# circuit.net
KiCad netlist of a schematic drawn in EAGLE
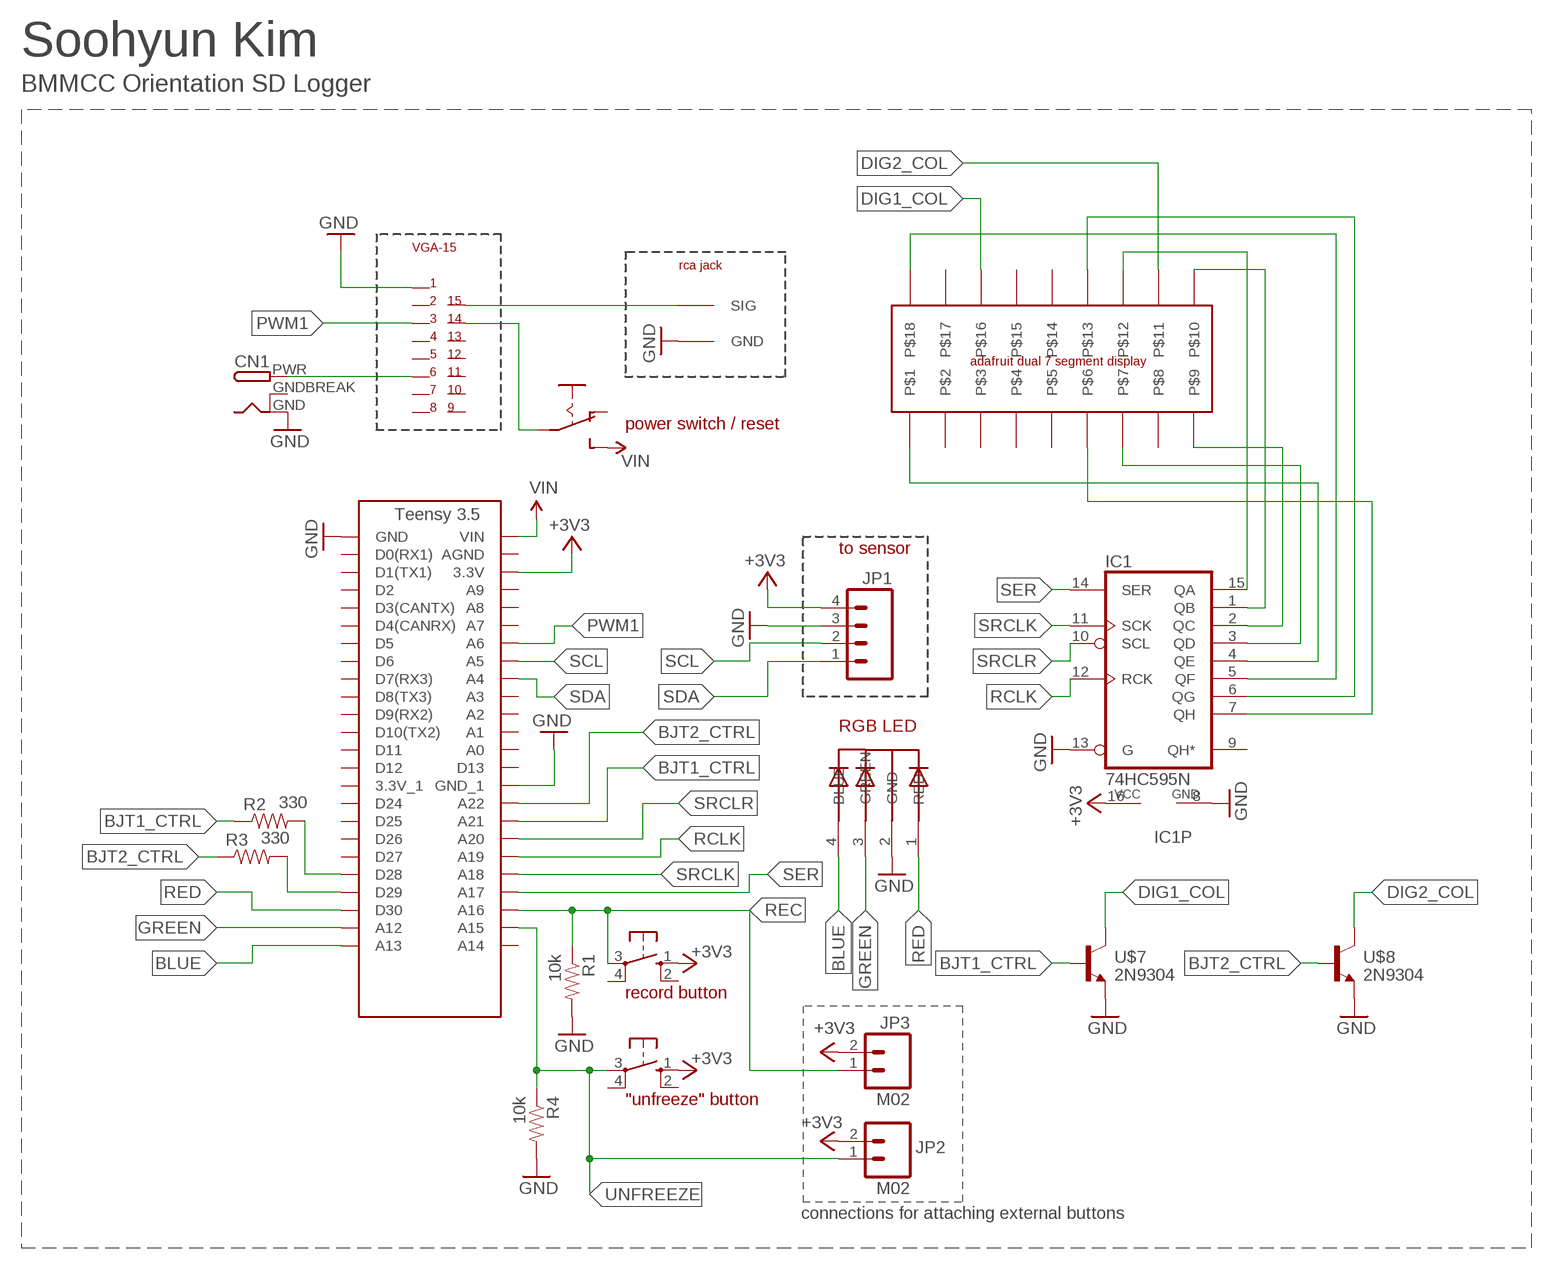
[diagram p0: schematic, sheet 1]

(export (version "E")
  (design (tool "Eeschema 10.0.6"))
  (components
    (comp (ref "CN1")
      (value "DCBARRELPTH")
      (footprint "eagle-import:DCJACK_2MM_PTH")
      (libsource (lib "eagle-import") (part "DCBARRELPTH"))
    )
    (comp (ref "IC1")
      (value "74HC595N")
      (footprint "eagle-import:DIL16")
      (libsource (lib "eagle-import") (part "74595NHC"))
    )
    (comp (ref "JP1")
      (value "M04")
      (footprint "eagle-import:1X04")
      (libsource (lib "eagle-import") (part "M04"))
    )
    (comp (ref "JP2")
      (value "M02")
      (footprint "eagle-import:1X02")
      (libsource (lib "eagle-import") (part "M02"))
    )
    (comp (ref "JP3")
      (value "M02")
      (footprint "eagle-import:1X02")
      (libsource (lib "eagle-import") (part "M02"))
    )
    (comp (ref "R1")
      (value "10k")
      (footprint "eagle-import:AXIAL-0.4")
      (libsource (lib "eagle-import") (part "RESISTORPTH-1/4W"))
    )
    (comp (ref "R2")
      (value "330")
      (footprint "eagle-import:AXIAL-0.4")
      (libsource (lib "eagle-import") (part "RESISTORPTH-1/4W"))
    )
    (comp (ref "R3")
      (value "330")
      (footprint "eagle-import:AXIAL-0.4")
      (libsource (lib "eagle-import") (part "RESISTORPTH-1/4W"))
    )
    (comp (ref "R4")
      (value "10k")
      (footprint "eagle-import:AXIAL-0.4")
      (libsource (lib "eagle-import") (part "RESISTORPTH-1/4W"))
    )
    (comp (ref "S3")
      (value "40-XX")
      (footprint "eagle-import:B3F-40XX")
      (fields (field (name "MF") "OMRON COMPONENTS USA") (field (name "MPN") "B3F-4000"))
      (libsource (lib "eagle-import") (part "40-XX"))
    )
    (comp (ref "S4")
      (value "40-XX")
      (footprint "eagle-import:B3F-40XX")
      (fields (field (name "MF") "OMRON COMPONENTS USA") (field (name "MPN") "B3F-4000"))
      (libsource (lib "eagle-import") (part "40-XX"))
    )
    (comp (ref "U$1")
      (value "TEENSY_3.5")
      (footprint "eagle-import:TEENSY_3.5_SIMPLE")
      (libsource (lib "eagle-import") (part "TEENSY_3.5"))
    )
    (comp (ref "U$2")
      (value "VGA-15")
      (footprint "eagle-import:VGA-15")
      (libsource (lib "eagle-import") (part "VGA-15"))
    )
    (comp (ref "U$3")
      (value "RCA")
      (footprint "eagle-import:RCA")
      (libsource (lib "eagle-import") (part "RCA"))
    )
    (comp (ref "U$4")
      (value "LED_5MM_RGB")
      (footprint "eagle-import:LED_5MM_RGB")
      (libsource (lib "eagle-import") (part "LED_5MM_RGB"))
    )
    (comp (ref "U$5")
      (value "SLIDE_SWITCH")
      (footprint "eagle-import:SLIDE_SWITCH")
      (libsource (lib "eagle-import") (part "SLIDE_SWITCH"))
    )
    (comp (ref "U$6")
      (value "DUAL_7SEG_DISPLAY")
      (footprint "eagle-import:DUAL_7SEG_DISPLAY")
      (libsource (lib "eagle-import") (part "DUAL_7SEG_DISPLAY"))
    )
    (comp (ref "U$7")
      (value "2N9304")
      (footprint "eagle-import:TO92")
      (libsource (lib "eagle-import") (part "2N9304"))
    )
    (comp (ref "U$8")
      (value "2N9304")
      (footprint "eagle-import:TO92")
      (libsource (lib "eagle-import") (part "2N9304"))
    )
  )
  (nets
    (net (code "1") (name "+3V3") (class "Default")
      (node (ref "IC1") (pin "16") (pinfunction "VCC_16") (pintype "power_in"))
      (node (ref "JP1") (pin "4") (pinfunction "4_4") (pintype "passive"))
      (node (ref "JP2") (pin "2") (pinfunction "2_2") (pintype "passive"))
      (node (ref "JP3") (pin "2") (pinfunction "2_2") (pintype "passive"))
      (node (ref "S3") (pin "1") (pinfunction "S_1") (pintype "passive"))
      (node (ref "S4") (pin "1") (pinfunction "S_1") (pintype "passive"))
      (node (ref "U$1") (pin "3.3V") (pinfunction "3.3V_3.3V") (pintype "bidirectional"))
    )
    (net (code "2") (name "/GNDBREAK") (class "Default")
      (node (ref "CN1") (pin "GNDBREAK") (pinfunction "GNDBREAK_GNDBREAK") (pintype "power_in"))
    )
    (net (code "3") (name "BJT1_CTRL") (class "Default")
      (node (ref "R2") (pin "P$1") (pinfunction "1_P$1") (pintype "passive"))
      (node (ref "U$1") (pin "A21") (pinfunction "A21_A21") (pintype "bidirectional"))
      (node (ref "U$7") (pin "2") (pinfunction "BASE_2") (pintype "passive"))
    )
    (net (code "4") (name "BJT2_CTRL") (class "Default")
      (node (ref "R3") (pin "P$1") (pinfunction "1_P$1") (pintype "passive"))
      (node (ref "U$1") (pin "A22") (pinfunction "A22_A22") (pintype "bidirectional"))
      (node (ref "U$8") (pin "2") (pinfunction "BASE_2") (pintype "passive"))
    )
    (net (code "5") (name "BLUE") (class "Default")
      (node (ref "U$1") (pin "A13") (pinfunction "A13_A13") (pintype "bidirectional"))
      (node (ref "U$4") (pin "4") (pinfunction "BLUE_4") (pintype "bidirectional"))
    )
    (net (code "6") (name "DIG1_COL") (class "Default")
      (node (ref "U$6") (pin "16") (pinfunction "P$16_16") (pintype "bidirectional"))
      (node (ref "U$7") (pin "1") (pinfunction "COLLECTOR_1") (pintype "passive"))
    )
    (net (code "7") (name "DIG2_COL") (class "Default")
      (node (ref "U$6") (pin "11") (pinfunction "P$11_11") (pintype "bidirectional"))
      (node (ref "U$8") (pin "1") (pinfunction "COLLECTOR_1") (pintype "passive"))
    )
    (net (code "8") (name "GND") (class "Default")
      (node (ref "CN1") (pin "GND") (pinfunction "GND_GND") (pintype "power_in"))
      (node (ref "IC1") (pin "13") (pinfunction "G_13") (pintype "input"))
      (node (ref "IC1") (pin "8") (pinfunction "GND_8") (pintype "power_in"))
      (node (ref "JP1") (pin "3") (pinfunction "3_3") (pintype "passive"))
      (node (ref "R1") (pin "P$2") (pinfunction "2_P$2") (pintype "passive"))
      (node (ref "R4") (pin "P$2") (pinfunction "2_P$2") (pintype "passive"))
      (node (ref "U$1") (pin "GND") (pinfunction "GND_GND") (pintype "bidirectional"))
      (node (ref "U$1") (pin "GND_1") (pinfunction "GND_1_GND_1") (pintype "bidirectional"))
      (node (ref "U$2") (pin "1") (pinfunction "P$1_1") (pintype "bidirectional"))
      (node (ref "U$3") (pin "GND") (pinfunction "GND_GND") (pintype "bidirectional"))
      (node (ref "U$4") (pin "2") (pinfunction "GND_2") (pintype "bidirectional"))
      (node (ref "U$7") (pin "3") (pinfunction "EMITTER_3") (pintype "passive"))
      (node (ref "U$8") (pin "3") (pinfunction "EMITTER_3") (pintype "passive"))
    )
    (net (code "9") (name "GREEN") (class "Default")
      (node (ref "U$1") (pin "A12") (pinfunction "A12_A12") (pintype "bidirectional"))
      (node (ref "U$4") (pin "3") (pinfunction "GREEN_3") (pintype "bidirectional"))
    )
    (net (code "10") (name "Net-(IC1A-QA)") (class "Default")
      (node (ref "IC1") (pin "15") (pinfunction "QA_15") (pintype "tri_state"))
      (node (ref "U$6") (pin "12") (pinfunction "P$12_12") (pintype "bidirectional"))
    )
    (net (code "11") (name "Net-(IC1A-QB)") (class "Default")
      (node (ref "IC1") (pin "1") (pinfunction "QB_1") (pintype "tri_state"))
      (node (ref "U$6") (pin "10") (pinfunction "P$10_10") (pintype "bidirectional"))
    )
    (net (code "12") (name "Net-(IC1A-QC)") (class "Default")
      (node (ref "IC1") (pin "2") (pinfunction "QC_2") (pintype "tri_state"))
      (node (ref "U$6") (pin "9") (pinfunction "P$9_9") (pintype "bidirectional"))
    )
    (net (code "13") (name "Net-(IC1A-QD)") (class "Default")
      (node (ref "IC1") (pin "3") (pinfunction "QD_3") (pintype "tri_state"))
      (node (ref "U$6") (pin "7") (pinfunction "P$7_7") (pintype "bidirectional"))
    )
    (net (code "14") (name "Net-(IC1A-QE)") (class "Default")
      (node (ref "IC1") (pin "4") (pinfunction "QE_4") (pintype "tri_state"))
      (node (ref "U$6") (pin "1") (pinfunction "P$1_1") (pintype "bidirectional"))
    )
    (net (code "15") (name "Net-(IC1A-QF)") (class "Default")
      (node (ref "IC1") (pin "5") (pinfunction "QF_5") (pintype "tri_state"))
      (node (ref "U$6") (pin "18") (pinfunction "P$18_18") (pintype "bidirectional"))
    )
    (net (code "16") (name "Net-(IC1A-QG)") (class "Default")
      (node (ref "IC1") (pin "6") (pinfunction "QG_6") (pintype "tri_state"))
      (node (ref "U$6") (pin "13") (pinfunction "P$13_13") (pintype "bidirectional"))
    )
    (net (code "17") (name "Net-(IC1A-QH)") (class "Default")
      (node (ref "IC1") (pin "7") (pinfunction "QH_7") (pintype "tri_state"))
      (node (ref "U$6") (pin "6") (pinfunction "P$6_6") (pintype "bidirectional"))
    )
    (net (code "18") (name "Net-(R2-2)") (class "Default")
      (node (ref "R2") (pin "P$2") (pinfunction "2_P$2") (pintype "passive"))
      (node (ref "U$1") (pin "D28") (pinfunction "D28_D28") (pintype "bidirectional"))
    )
    (net (code "19") (name "Net-(R3-2)") (class "Default")
      (node (ref "R3") (pin "P$2") (pinfunction "2_P$2") (pintype "passive"))
      (node (ref "U$1") (pin "D29") (pinfunction "D29_D29") (pintype "bidirectional"))
    )
    (net (code "20") (name "Net-(U$2-P$6)") (class "Default")
      (node (ref "CN1") (pin "PWR") (pinfunction "PWR_PWR") (pintype "power_in"))
      (node (ref "U$2") (pin "6") (pinfunction "P$6_6") (pintype "bidirectional"))
    )
    (net (code "21") (name "Net-(U$2-P$14)") (class "Default")
      (node (ref "U$2") (pin "14") (pinfunction "P$14_14") (pintype "bidirectional"))
      (node (ref "U$5") (pin "P$2") (pinfunction "P_P$2") (pintype "passive"))
    )
    (net (code "22") (name "Net-(U$2-P$15)") (class "Default")
      (node (ref "U$2") (pin "15") (pinfunction "P$15_15") (pintype "bidirectional"))
      (node (ref "U$3") (pin "SIG") (pinfunction "SIG_SIG") (pintype "bidirectional"))
    )
    (net (code "23") (name "PWM1") (class "Default")
      (node (ref "U$1") (pin "A6") (pinfunction "A6_A6") (pintype "bidirectional"))
      (node (ref "U$2") (pin "3") (pinfunction "P$3_3") (pintype "bidirectional"))
    )
    (net (code "24") (name "RCLK") (class "Default")
      (node (ref "IC1") (pin "12") (pinfunction "RCK_12") (pintype "input"))
      (node (ref "U$1") (pin "A19") (pinfunction "A19_A19") (pintype "bidirectional"))
    )
    (net (code "25") (name "REC") (class "Default")
      (node (ref "JP3") (pin "1") (pinfunction "1_1") (pintype "passive"))
      (node (ref "R1") (pin "P$1") (pinfunction "1_P$1") (pintype "passive"))
      (node (ref "S3") (pin "3") (pinfunction "P_3") (pintype "passive"))
      (node (ref "U$1") (pin "A16") (pinfunction "A16_A16") (pintype "bidirectional"))
    )
    (net (code "26") (name "RED") (class "Default")
      (node (ref "U$1") (pin "D30") (pinfunction "D30_D30") (pintype "bidirectional"))
      (node (ref "U$4") (pin "1") (pinfunction "RED_1") (pintype "bidirectional"))
    )
    (net (code "27") (name "SCL") (class "Default")
      (node (ref "JP1") (pin "2") (pinfunction "2_2") (pintype "passive"))
      (node (ref "U$1") (pin "A5") (pinfunction "A5_A5") (pintype "bidirectional"))
    )
    (net (code "28") (name "SDA") (class "Default")
      (node (ref "JP1") (pin "1") (pinfunction "1_1") (pintype "passive"))
      (node (ref "U$1") (pin "A4") (pinfunction "A4_A4") (pintype "bidirectional"))
    )
    (net (code "29") (name "SER") (class "Default")
      (node (ref "IC1") (pin "14") (pinfunction "SER_14") (pintype "input"))
      (node (ref "U$1") (pin "A17") (pinfunction "A17_A17") (pintype "bidirectional"))
    )
    (net (code "30") (name "SRCLK") (class "Default")
      (node (ref "IC1") (pin "11") (pinfunction "SCK_11") (pintype "input"))
      (node (ref "U$1") (pin "A18") (pinfunction "A18_A18") (pintype "bidirectional"))
    )
    (net (code "31") (name "SRCLR") (class "Default")
      (node (ref "IC1") (pin "10") (pinfunction "SCL_10") (pintype "input"))
      (node (ref "U$1") (pin "A20") (pinfunction "A20_A20") (pintype "bidirectional"))
    )
    (net (code "32") (name "UNFREEZE") (class "Default")
      (node (ref "JP2") (pin "1") (pinfunction "1_1") (pintype "passive"))
      (node (ref "R4") (pin "P$1") (pinfunction "1_P$1") (pintype "passive"))
      (node (ref "S4") (pin "3") (pinfunction "P_3") (pintype "passive"))
      (node (ref "U$1") (pin "A15") (pinfunction "A15_A15") (pintype "bidirectional"))
    )
    (net (code "33") (name "VIN") (class "Default")
      (node (ref "U$1") (pin "VIN") (pinfunction "VIN_VIN") (pintype "bidirectional"))
      (node (ref "U$5") (pin "P$3") (pinfunction "S_P$3") (pintype "passive"))
    )
    (net (code "34") (name "unconnected-(IC1A-QH*-Pad9)") (class "Default")
      (node (ref "IC1") (pin "9") (pinfunction "QH*_9") (pintype "tri_state"))
    )
    (net (code "35") (name "unconnected-(S3-P1-Pad4)") (class "Default")
      (node (ref "S3") (pin "4") (pinfunction "P1_4") (pintype "passive"))
    )
    (net (code "36") (name "unconnected-(S3-S1-Pad2)") (class "Default")
      (node (ref "S3") (pin "2") (pinfunction "S1_2") (pintype "passive"))
    )
    (net (code "37") (name "unconnected-(S4-P1-Pad4)") (class "Default")
      (node (ref "S4") (pin "4") (pinfunction "P1_4") (pintype "passive"))
    )
    (net (code "38") (name "unconnected-(S4-S1-Pad2)") (class "Default")
      (node (ref "S4") (pin "2") (pinfunction "S1_2") (pintype "passive"))
    )
    (net (code "39") (name "unconnected-(U$1-Pad3.3V_1)") (class "Default")
      (node (ref "U$1") (pin "3.3V_1") (pinfunction "3.3V_1_3.3V_1") (pintype "bidirectional"))
    )
    (net (code "40") (name "unconnected-(U$1-PadA0)") (class "Default")
      (node (ref "U$1") (pin "A0") (pinfunction "A0_A0") (pintype "bidirectional"))
    )
    (net (code "41") (name "unconnected-(U$1-PadA1)") (class "Default")
      (node (ref "U$1") (pin "A1") (pinfunction "A1_A1") (pintype "bidirectional"))
    )
    (net (code "42") (name "unconnected-(U$1-PadA2)") (class "Default")
      (node (ref "U$1") (pin "A2") (pinfunction "A2_A2") (pintype "bidirectional"))
    )
    (net (code "43") (name "unconnected-(U$1-PadA3)") (class "Default")
      (node (ref "U$1") (pin "A3") (pinfunction "A3_A3") (pintype "bidirectional"))
    )
    (net (code "44") (name "unconnected-(U$1-PadA7)") (class "Default")
      (node (ref "U$1") (pin "A7") (pinfunction "A7_A7") (pintype "bidirectional"))
    )
    (net (code "45") (name "unconnected-(U$1-PadA8)") (class "Default")
      (node (ref "U$1") (pin "A8") (pinfunction "A8_A8") (pintype "bidirectional"))
    )
    (net (code "46") (name "unconnected-(U$1-PadA9)") (class "Default")
      (node (ref "U$1") (pin "A9") (pinfunction "A9_A9") (pintype "bidirectional"))
    )
    (net (code "47") (name "unconnected-(U$1-PadA14)") (class "Default")
      (node (ref "U$1") (pin "A14") (pinfunction "A14_A14") (pintype "bidirectional"))
    )
    (net (code "48") (name "unconnected-(U$1-PadAGND)") (class "Default")
      (node (ref "U$1") (pin "AGND") (pinfunction "AGND_AGND") (pintype "bidirectional"))
    )
    (net (code "49") (name "unconnected-(U$1-PadD0(RX1))") (class "Default")
      (node (ref "U$1") (pin "D0(RX1)") (pinfunction "D0(RX1)_D0(RX1)") (pintype "bidirectional"))
    )
    (net (code "50") (name "unconnected-(U$1-PadD1(TX1))") (class "Default")
      (node (ref "U$1") (pin "D1(TX1)") (pinfunction "D1(TX1)_D1(TX1)") (pintype "bidirectional"))
    )
    (net (code "51") (name "unconnected-(U$1-PadD2)") (class "Default")
      (node (ref "U$1") (pin "D2") (pinfunction "D2_D2") (pintype "bidirectional"))
    )
    (net (code "52") (name "unconnected-(U$1-PadD3(CANTX))") (class "Default")
      (node (ref "U$1") (pin "D3(CANTX)") (pinfunction "D3(CANTX)_D3(CANTX)") (pintype "bidirectional"))
    )
    (net (code "53") (name "unconnected-(U$1-PadD4(CANRX))") (class "Default")
      (node (ref "U$1") (pin "D4(CANRX)") (pinfunction "D4(CANRX)_D4(CANRX)") (pintype "bidirectional"))
    )
    (net (code "54") (name "unconnected-(U$1-PadD5)") (class "Default")
      (node (ref "U$1") (pin "D5") (pinfunction "D5_D5") (pintype "bidirectional"))
    )
    (net (code "55") (name "unconnected-(U$1-PadD6)") (class "Default")
      (node (ref "U$1") (pin "D6") (pinfunction "D6_D6") (pintype "bidirectional"))
    )
    (net (code "56") (name "unconnected-(U$1-PadD7(RX3))") (class "Default")
      (node (ref "U$1") (pin "D7(RX3)") (pinfunction "D7(RX3)_D7(RX3)") (pintype "bidirectional"))
    )
    (net (code "57") (name "unconnected-(U$1-PadD8(TX3))") (class "Default")
      (node (ref "U$1") (pin "D8(TX3)") (pinfunction "D8(TX3)_D8(TX3)") (pintype "bidirectional"))
    )
    (net (code "58") (name "unconnected-(U$1-PadD9(RX2))") (class "Default")
      (node (ref "U$1") (pin "D9(RX2)") (pinfunction "D9(RX2)_D9(RX2)") (pintype "bidirectional"))
    )
    (net (code "59") (name "unconnected-(U$1-PadD10(TX2))") (class "Default")
      (node (ref "U$1") (pin "D10(TX2)") (pinfunction "D10(TX2)_D10(TX2)") (pintype "bidirectional"))
    )
    (net (code "60") (name "unconnected-(U$1-PadD11)") (class "Default")
      (node (ref "U$1") (pin "D11") (pinfunction "D11_D11") (pintype "bidirectional"))
    )
    (net (code "61") (name "unconnected-(U$1-PadD12)") (class "Default")
      (node (ref "U$1") (pin "D12") (pinfunction "D12_D12") (pintype "bidirectional"))
    )
    (net (code "62") (name "unconnected-(U$1-PadD13)") (class "Default")
      (node (ref "U$1") (pin "D13") (pinfunction "D13_D13") (pintype "bidirectional"))
    )
    (net (code "63") (name "unconnected-(U$1-PadD24)") (class "Default")
      (node (ref "U$1") (pin "D24") (pinfunction "D24_D24") (pintype "bidirectional"))
    )
    (net (code "64") (name "unconnected-(U$1-PadD25)") (class "Default")
      (node (ref "U$1") (pin "D25") (pinfunction "D25_D25") (pintype "bidirectional"))
    )
    (net (code "65") (name "unconnected-(U$1-PadD26)") (class "Default")
      (node (ref "U$1") (pin "D26") (pinfunction "D26_D26") (pintype "bidirectional"))
    )
    (net (code "66") (name "unconnected-(U$1-PadD27)") (class "Default")
      (node (ref "U$1") (pin "D27") (pinfunction "D27_D27") (pintype "bidirectional"))
    )
    (net (code "67") (name "unconnected-(U$2-P$2-Pad2)") (class "Default")
      (node (ref "U$2") (pin "2") (pinfunction "P$2_2") (pintype "bidirectional"))
    )
    (net (code "68") (name "unconnected-(U$2-P$4-Pad4)") (class "Default")
      (node (ref "U$2") (pin "4") (pinfunction "P$4_4") (pintype "bidirectional"))
    )
    (net (code "69") (name "unconnected-(U$2-P$5-Pad5)") (class "Default")
      (node (ref "U$2") (pin "5") (pinfunction "P$5_5") (pintype "bidirectional"))
    )
    (net (code "70") (name "unconnected-(U$2-P$7-Pad7)") (class "Default")
      (node (ref "U$2") (pin "7") (pinfunction "P$7_7") (pintype "bidirectional"))
    )
    (net (code "71") (name "unconnected-(U$2-P$8-Pad8)") (class "Default")
      (node (ref "U$2") (pin "8") (pinfunction "P$8_8") (pintype "bidirectional"))
    )
    (net (code "72") (name "unconnected-(U$2-P$9-Pad9)") (class "Default")
      (node (ref "U$2") (pin "9") (pinfunction "P$9_9") (pintype "bidirectional"))
    )
    (net (code "73") (name "unconnected-(U$2-P$10-Pad10)") (class "Default")
      (node (ref "U$2") (pin "10") (pinfunction "P$10_10") (pintype "bidirectional"))
    )
    (net (code "74") (name "unconnected-(U$2-P$11-Pad11)") (class "Default")
      (node (ref "U$2") (pin "11") (pinfunction "P$11_11") (pintype "bidirectional"))
    )
    (net (code "75") (name "unconnected-(U$2-P$12-Pad12)") (class "Default")
      (node (ref "U$2") (pin "12") (pinfunction "P$12_12") (pintype "bidirectional"))
    )
    (net (code "76") (name "unconnected-(U$2-P$13-Pad13)") (class "Default")
      (node (ref "U$2") (pin "13") (pinfunction "P$13_13") (pintype "bidirectional"))
    )
    (net (code "77") (name "unconnected-(U$5-O-PadP$1)") (class "Default")
      (node (ref "U$5") (pin "P$1") (pinfunction "O_P$1") (pintype "passive"))
    )
    (net (code "78") (name "unconnected-(U$6-P$2-Pad2)") (class "Default")
      (node (ref "U$6") (pin "2") (pinfunction "P$2_2") (pintype "bidirectional"))
    )
    (net (code "79") (name "unconnected-(U$6-P$3-Pad3)") (class "Default")
      (node (ref "U$6") (pin "3") (pinfunction "P$3_3") (pintype "bidirectional"))
    )
    (net (code "80") (name "unconnected-(U$6-P$4-Pad4)") (class "Default")
      (node (ref "U$6") (pin "4") (pinfunction "P$4_4") (pintype "bidirectional"))
    )
    (net (code "81") (name "unconnected-(U$6-P$5-Pad5)") (class "Default")
      (node (ref "U$6") (pin "5") (pinfunction "P$5_5") (pintype "bidirectional"))
    )
    (net (code "82") (name "unconnected-(U$6-P$8-Pad8)") (class "Default")
      (node (ref "U$6") (pin "8") (pinfunction "P$8_8") (pintype "bidirectional"))
    )
    (net (code "83") (name "unconnected-(U$6-P$14-Pad14)") (class "Default")
      (node (ref "U$6") (pin "14") (pinfunction "P$14_14") (pintype "bidirectional"))
    )
    (net (code "84") (name "unconnected-(U$6-P$15-Pad15)") (class "Default")
      (node (ref "U$6") (pin "15") (pinfunction "P$15_15") (pintype "bidirectional"))
    )
    (net (code "85") (name "unconnected-(U$6-P$17-Pad17)") (class "Default")
      (node (ref "U$6") (pin "17") (pinfunction "P$17_17") (pintype "bidirectional"))
    )
  )
)
